# TEMP_IMU_NAND.net
KiCad netlist of a schematic drawn in Altium Designer
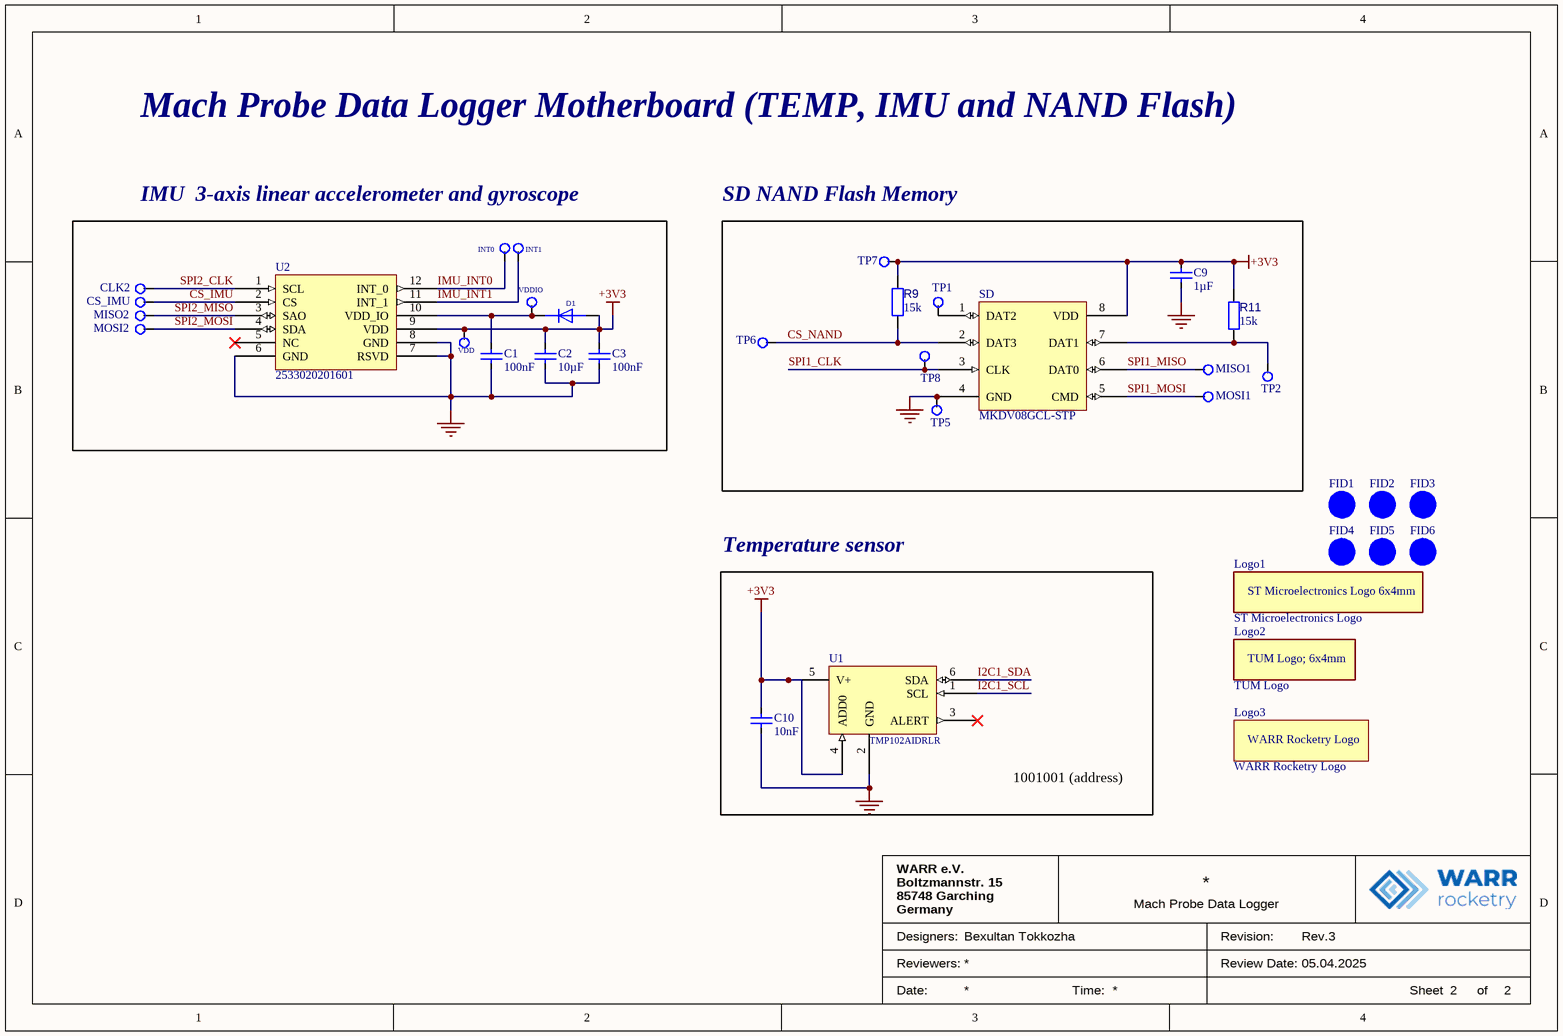
[diagram p0: TEMP_IMU_NAND.SchDoc]

(export (version "E")
  (design (tool "Eeschema 10.0.6"))
  (components
    (comp (ref "C1")
      (value "100nF")
      (footprint "CAP_0603")
      (fields (field (name "Comment") "C_0603_100n_5%_50V"))
      (libsource (lib "WARR Rocketry Electronics") (part "Capacitor"))
    )
    (comp (ref "C2")
      (value "10µF")
      (footprint "GCM188R71E224KA55J")
      (fields (field (name "Comment") "C_0603_10uF"))
      (libsource (lib "WARR Rocketry Electronics") (part "Capacitor"))
    )
    (comp (ref "C3")
      (value "100nF")
      (footprint "CAP_0603")
      (fields (field (name "Comment") "C_0603_100n_5%_50V"))
      (libsource (lib "WARR Rocketry Electronics") (part "Capacitor"))
    )
    (comp (ref "C9")
      (value "1µF")
      (footprint "CAP_0603")
      (description "Ceramic Capacitor, Multilayer, Ceramic, 50V, 10% +Tol, 10% -Tol, 1uF, Surface Mount, 0603")
      (fields (field (name "Comment") "C_0603_1u_10%_50V"))
      (libsource (lib "WARR Rocketry Electronics") (part "Capacitor"))
    )
    (comp (ref "C10")
      (value "10nF")
      (footprint "CAP_0603")
      (fields (field (name "TOLERANCE") "5%") (field (name "Comment") "C_0603_10n_5%_50V"))
      (libsource (lib "WARR Rocketry Electronics") (part "Capacitor"))
    )
    (comp (ref "CLK2")
      (value "Testpoint")
      (footprint "Testpoint-Footprint-1")
      (description "Schematic for Testpoint")
      (libsource (lib "WARR Rocketry Electronics") (part "TP?"))
    )
    (comp (ref "CS_IMU")
      (value "Testpoint")
      (footprint "Testpoint-Footprint-1")
      (description "Schematic for Testpoint")
      (libsource (lib "WARR Rocketry Electronics") (part "TP?"))
    )
    (comp (ref "D1")
      (value "BAT60A")
      (footprint "BAT60A")
      (description "Rectifier Diode, Shottky, 3A, 10V")
      (libsource (lib "WARR Rocketry Electronics") (part "DIODE-2"))
    )
    (comp (ref "FID1")
      (value "Fiducial")
      (footprint "Fiducial_1mm")
      (description "1mm Fiducial")
      (libsource (lib "WARR Rocketry Electronics") (part "Fiducial"))
    )
    (comp (ref "FID2")
      (value "Fiducial")
      (footprint "Fiducial_1mm")
      (description "1mm Fiducial")
      (libsource (lib "WARR Rocketry Electronics") (part "Fiducial"))
    )
    (comp (ref "FID3")
      (value "Fiducial")
      (footprint "Fiducial_1mm")
      (description "1mm Fiducial")
      (libsource (lib "WARR Rocketry Electronics") (part "Fiducial"))
    )
    (comp (ref "FID4")
      (value "Fiducial")
      (footprint "Fiducial_1mm")
      (description "1mm Fiducial")
      (libsource (lib "WARR Rocketry Electronics") (part "Fiducial"))
    )
    (comp (ref "FID5")
      (value "Fiducial")
      (footprint "Fiducial_1mm")
      (description "1mm Fiducial")
      (libsource (lib "WARR Rocketry Electronics") (part "Fiducial"))
    )
    (comp (ref "FID6")
      (value "Fiducial")
      (footprint "Fiducial_1mm")
      (description "1mm Fiducial")
      (libsource (lib "WARR Rocketry Electronics") (part "Fiducial"))
    )
    (comp (ref "INT0")
      (value "Testpoint")
      (footprint "Testpoint-Footprint-1")
      (description "Schematic for Testpoint")
      (libsource (lib "WARR Rocketry Electronics") (part "TP?"))
    )
    (comp (ref "INT1")
      (value "Testpoint")
      (footprint "Testpoint-Footprint-1")
      (description "Schematic for Testpoint")
      (libsource (lib "WARR Rocketry Electronics") (part "TP?"))
    )
    (comp (ref "Logo1")
      (value "ST Microelectronics Logo")
      (footprint "New footprint 1")
      (description "ST Microelectronics Logo 6x4mm")
      (libsource (lib "WARR Rocketry Electronics") (part "ST Microelectronics Logo"))
    )
    (comp (ref "Logo2")
      (value "TUM Logo")
      (footprint "New footprint 1")
      (description "6 x 4 mm TUM Logo")
      (libsource (lib "WARR Rocketry Electronics") (part "TUM Logo"))
    )
    (comp (ref "Logo3")
      (value "WARR Rocketry Logo")
      (footprint "WARR Rocketry Logo-Footprint-1")
      (description "Warr Rocketry Logo")
      (libsource (lib "WARR Rocketry Electronics") (part "WARR Rocketry Logo-Symbol-1"))
    )
    (comp (ref "MISO1")
      (value "Testpoint")
      (footprint "Testpoint-Footprint-1")
      (description "Schematic for Testpoint")
      (libsource (lib "WARR Rocketry Electronics") (part "TP?"))
    )
    (comp (ref "MISO2")
      (value "Testpoint")
      (footprint "Testpoint-Footprint-1")
      (description "Schematic for Testpoint")
      (libsource (lib "WARR Rocketry Electronics") (part "TP?"))
    )
    (comp (ref "MOSI1")
      (value "Testpoint")
      (footprint "Testpoint-Footprint-1")
      (description "Schematic for Testpoint")
      (libsource (lib "WARR Rocketry Electronics") (part "TP?"))
    )
    (comp (ref "MOSI2")
      (value "Testpoint")
      (footprint "Testpoint-Footprint-1")
      (description "Schematic for Testpoint")
      (libsource (lib "WARR Rocketry Electronics") (part "TP?"))
    )
    (comp (ref "R9")
      (value "15k")
      (footprint "R_0603_Yageo")
      (fields
        (field (name "TOLERANCE") "1%")
        (field (name "POWER") "100mW")
        (field (name "Comment") "RES_0603_15k")
      )
      (libsource (lib "WARR Rocketry Electronics") (part "RES-2"))
    )
    (comp (ref "R11")
      (value "15k")
      (footprint "R_0603_Yageo")
      (fields
        (field (name "TOLERANCE") "1%")
        (field (name "POWER") "100mW")
        (field (name "Comment") "RES_0603_15k")
      )
      (libsource (lib "WARR Rocketry Electronics") (part "RES-2"))
    )
    (comp (ref "SD")
      (value "MKDV08GCL-STP")
      (footprint "New footprint 1")
      (libsource (lib "WARR Rocketry Electronics") (part "New symbol 1"))
    )
    (comp (ref "TP1")
      (value "Testpoint")
      (footprint "Testpoint-Footprint-1")
      (description "Schematic for Testpoint")
      (libsource (lib "WARR Rocketry Electronics") (part "TP?"))
    )
    (comp (ref "TP2")
      (value "Testpoint")
      (footprint "Testpoint-Footprint-1")
      (description "Schematic for Testpoint")
      (libsource (lib "WARR Rocketry Electronics") (part "TP?"))
    )
    (comp (ref "TP5")
      (value "Testpoint")
      (footprint "Testpoint-Footprint-1")
      (description "Schematic for Testpoint")
      (libsource (lib "WARR Rocketry Electronics") (part "TP?"))
    )
    (comp (ref "TP6")
      (value "Testpoint")
      (footprint "Testpoint-Footprint-1")
      (description "Schematic for Testpoint")
      (libsource (lib "WARR Rocketry Electronics") (part "TP?"))
    )
    (comp (ref "TP7")
      (value "Testpoint")
      (footprint "Testpoint-Footprint-1")
      (description "Schematic for Testpoint")
      (libsource (lib "WARR Rocketry Electronics") (part "TP?"))
    )
    (comp (ref "TP8")
      (value "Testpoint")
      (footprint "Testpoint-Footprint-1")
      (description "Schematic for Testpoint")
      (libsource (lib "WARR Rocketry Electronics") (part "TP?"))
    )
    (comp (ref "U1")
      (value "TMP102AIDRLR")
      (footprint "SOTFL127P600-8N")
      (description "Digital Temperature Sensor, I2C,12 Bit(s), ±2C, SOT563")
      (fields
        (field (name "LCSC PART NUMBER") "C99269")
        (field (name "MOUSER PART NUMBER") "595-TMP102AIDRLR")
      )
      (libsource (lib "WARR Rocketry") (part "TMP102AIDRLR-Symbol-1"))
    )
    (comp (ref "U2")
      (value "2533020201601")
      (footprint "QFN50P200X200X70-12N")
      (description "WSEN-ITDS Accelerometer X, Y, Z Axis ±2g, 4g, 8g, 16g 0.08Hz ~ 400Hz 12-LGA (2x2)")
      (libsource (lib "WARR Rocketry Electronics") (part "2533020201601-Symbol-1"))
    )
    (comp (ref "VDD")
      (value "Testpoint")
      (footprint "Testpoint-Footprint-1")
      (description "Schematic for Testpoint")
      (libsource (lib "WARR Rocketry Electronics") (part "TP?"))
    )
    (comp (ref "VDDIO")
      (value "Testpoint")
      (footprint "Testpoint-Footprint-1")
      (description "Schematic for Testpoint")
      (libsource (lib "WARR Rocketry Electronics") (part "TP?"))
    )
  )
  (nets
    (net (code "1") (name "+3V3") (class "Default")
      (node (ref "C10") (pin "1") (pinfunction "1_1") (pintype "passive"))
      (node (ref "C2") (pin "1") (pinfunction "1_1") (pintype "passive"))
      (node (ref "C3") (pin "1") (pinfunction "1_1") (pintype "passive"))
      (node (ref "C9") (pin "1") (pinfunction "1_1") (pintype "passive"))
      (node (ref "D1") (pin "1") (pinfunction "A_1") (pintype "passive"))
      (node (ref "R11") (pin "2") (pinfunction "2_2") (pintype "passive"))
      (node (ref "R9") (pin "2") (pinfunction "2_2") (pintype "passive"))
      (node (ref "SD") (pin "8") (pinfunction "VDD_8") (pintype "power_in"))
      (node (ref "TP7") (pin "1") (pinfunction "1_1") (pintype "passive"))
      (node (ref "U1") (pin "4") (pinfunction "ADD0_4") (pintype "input"))
      (node (ref "U1") (pin "5") (pinfunction "V+_5") (pintype "power_in"))
      (node (ref "U2") (pin "9") (pinfunction "VDD_9") (pintype "power_in"))
      (node (ref "VDD") (pin "1") (pinfunction "1_1") (pintype "passive"))
    )
    (net (code "2") (name "/CS_IMU") (class "Default")
      (node (ref "CS_IMU") (pin "1") (pinfunction "1_1") (pintype "passive"))
      (node (ref "U2") (pin "2") (pinfunction "CS_2") (pintype "input"))
    )
    (net (code "3") (name "/CS_NAND") (class "Default")
      (node (ref "R9") (pin "1") (pinfunction "1_1") (pintype "passive"))
      (node (ref "SD") (pin "2") (pinfunction "DAT3_2") (pintype "bidirectional"))
      (node (ref "TP6") (pin "1") (pinfunction "1_1") (pintype "passive"))
    )
    (net (code "4") (name "/I2C1_SCL") (class "Default")
      (node (ref "U1") (pin "1") (pinfunction "SCL_1") (pintype "input"))
    )
    (net (code "5") (name "/I2C1_SDA") (class "Default")
      (node (ref "U1") (pin "6") (pinfunction "SDA_6") (pintype "bidirectional"))
    )
    (net (code "6") (name "/IMU_INT0") (class "Default")
      (node (ref "INT0") (pin "1") (pinfunction "1_1") (pintype "passive"))
      (node (ref "U2") (pin "12") (pinfunction "INT_0_12") (pintype "output"))
    )
    (net (code "7") (name "/IMU_INT1") (class "Default")
      (node (ref "INT1") (pin "1") (pinfunction "1_1") (pintype "passive"))
      (node (ref "U2") (pin "11") (pinfunction "INT_1_11") (pintype "output"))
    )
    (net (code "8") (name "/SPI1_CLK") (class "Default")
      (node (ref "SD") (pin "3") (pinfunction "CLK_3") (pintype "input"))
      (node (ref "TP8") (pin "1") (pinfunction "1_1") (pintype "passive"))
    )
    (net (code "9") (name "/SPI1_MISO") (class "Default")
      (node (ref "MISO1") (pin "1") (pinfunction "1_1") (pintype "passive"))
      (node (ref "SD") (pin "6") (pinfunction "DAT0_6") (pintype "bidirectional"))
    )
    (net (code "10") (name "/SPI1_MOSI") (class "Default")
      (node (ref "MOSI1") (pin "1") (pinfunction "1_1") (pintype "passive"))
      (node (ref "SD") (pin "5") (pinfunction "CMD_5") (pintype "bidirectional"))
    )
    (net (code "11") (name "/SPI2_CLK") (class "Default")
      (node (ref "CLK2") (pin "1") (pinfunction "1_1") (pintype "passive"))
      (node (ref "U2") (pin "1") (pinfunction "SCL_1") (pintype "input"))
    )
    (net (code "12") (name "/SPI2_MISO") (class "Default")
      (node (ref "MISO2") (pin "1") (pinfunction "1_1") (pintype "passive"))
      (node (ref "U2") (pin "3") (pinfunction "SAO_3") (pintype "bidirectional"))
    )
    (net (code "13") (name "/SPI2_MOSI") (class "Default")
      (node (ref "MOSI2") (pin "1") (pinfunction "1_1") (pintype "passive"))
      (node (ref "U2") (pin "4") (pinfunction "SDA_4") (pintype "bidirectional"))
    )
    (net (code "14") (name "GND") (class "Default")
      (node (ref "C1") (pin "1") (pinfunction "1_1") (pintype "passive"))
      (node (ref "C10") (pin "2") (pinfunction "2_2") (pintype "passive"))
      (node (ref "C2") (pin "2") (pinfunction "2_2") (pintype "passive"))
      (node (ref "C3") (pin "2") (pinfunction "2_2") (pintype "passive"))
      (node (ref "C9") (pin "2") (pinfunction "2_2") (pintype "passive"))
      (node (ref "SD") (pin "4") (pinfunction "GND_4") (pintype "power_in"))
      (node (ref "TP5") (pin "1") (pinfunction "1_1") (pintype "passive"))
      (node (ref "U1") (pin "2") (pinfunction "GND_2") (pintype "power_in"))
      (node (ref "U2") (pin "6") (pinfunction "GND_6") (pintype "power_in"))
      (node (ref "U2") (pin "7") (pinfunction "RSVD_7") (pintype "passive"))
      (node (ref "U2") (pin "8") (pinfunction "GND_8") (pintype "power_in"))
    )
    (net (code "15") (name "Net-(D1-K)") (class "Default")
      (node (ref "C1") (pin "2") (pinfunction "2_2") (pintype "passive"))
      (node (ref "D1") (pin "2") (pinfunction "K_2") (pintype "passive"))
      (node (ref "U2") (pin "10") (pinfunction "VDD_IO_10") (pintype "power_in"))
      (node (ref "VDDIO") (pin "1") (pinfunction "1_1") (pintype "passive"))
    )
    (net (code "16") (name "Net-(SD-DAT1)") (class "Default")
      (node (ref "R11") (pin "1") (pinfunction "1_1") (pintype "passive"))
      (node (ref "SD") (pin "7") (pinfunction "DAT1_7") (pintype "bidirectional"))
      (node (ref "TP2") (pin "1") (pinfunction "1_1") (pintype "passive"))
    )
    (net (code "17") (name "Net-(SD-DAT2)") (class "Default")
      (node (ref "SD") (pin "1") (pinfunction "DAT2_1") (pintype "bidirectional"))
      (node (ref "TP1") (pin "1") (pinfunction "1_1") (pintype "passive"))
    )
    (net (code "18") (name "unconnected-(U1-ALERT-Pad3)") (class "Default")
      (node (ref "U1") (pin "3") (pinfunction "ALERT_3") (pintype "output+no_connect"))
    )
    (net (code "19") (name "unconnected-(U2-NC-Pad5)") (class "Default")
      (node (ref "U2") (pin "5") (pinfunction "NC_5") (pintype "passive+no_connect"))
    )
  )
)
